# Sheet2.net
KiCad netlist of a schematic drawn in Altium Designer
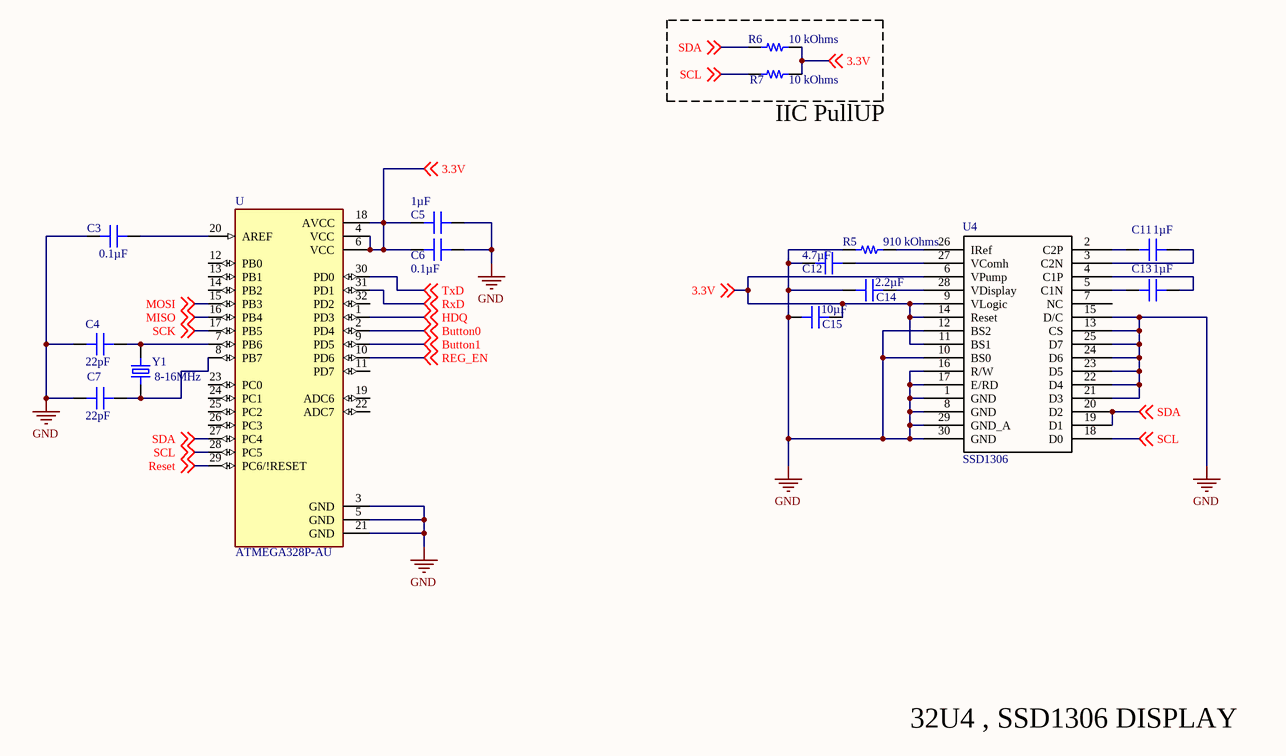
[diagram p0: Sheet2.SchDoc]

(export (version "E")
  (design (tool "Eeschema 10.0.6"))
  (components
    (comp (ref "C3")
      (value "0.1µF")
      (footprint "CAP 0402_1005")
      (description "CAP CER 10UF 10V X5R 0402")
      (fields
        (field (name "PART NUMBER") "CL05A106MP8NUB8")
        (field (name "MANUFACTURER") "Samsung Electro-Mechanics")
      )
      (libsource (lib "Celestial Altium Library - altium_library") (part "Capacitor"))
    )
    (comp (ref "C4")
      (value "22pF")
      (footprint "CAP 0402_1005")
      (description "CAP CER 10UF 10V X5R 0402")
      (fields
        (field (name "PART NUMBER") "CL05A106MP8NUB8")
        (field (name "MANUFACTURER") "Samsung Electro-Mechanics")
      )
      (libsource (lib "Celestial Altium Library - altium_library") (part "Capacitor"))
    )
    (comp (ref "C5")
      (value "1µF")
      (footprint "CAP 0402_1005")
      (description "CAP CER 10UF 10V X5R 0402")
      (fields
        (field (name "PART NUMBER") "CL05A106MP8NUB8")
        (field (name "MANUFACTURER") "Samsung Electro-Mechanics")
      )
      (libsource (lib "Celestial Altium Library - altium_library") (part "Capacitor"))
    )
    (comp (ref "C6")
      (value "0.1µF")
      (footprint "CAP 0402_1005")
      (description "CAP CER 10UF 10V X5R 0402")
      (fields
        (field (name "PART NUMBER") "CL05A106MP8NUB8")
        (field (name "MANUFACTURER") "Samsung Electro-Mechanics")
      )
      (libsource (lib "Celestial Altium Library - altium_library") (part "Capacitor"))
    )
    (comp (ref "C7")
      (value "22pF")
      (footprint "CAP 0402_1005")
      (description "CAP CER 10UF 10V X5R 0402")
      (fields
        (field (name "PART NUMBER") "CL05A106MP8NUB8")
        (field (name "MANUFACTURER") "Samsung Electro-Mechanics")
      )
      (libsource (lib "Celestial Altium Library - altium_library") (part "Capacitor"))
    )
    (comp (ref "C11")
      (value "1µF")
      (footprint "CAP 0402_1005")
      (description "CAP CER 10UF 10V X5R 0402")
      (fields
        (field (name "PART NUMBER") "CL05A106MP8NUB8")
        (field (name "MANUFACTURER") "Samsung Electro-Mechanics")
      )
      (libsource (lib "Celestial Altium Library - altium_library") (part "Capacitor"))
    )
    (comp (ref "C12")
      (value "4.7µF")
      (footprint "CAP 0402_1005")
      (description "CAP CER 10UF 10V X5R 0402")
      (fields
        (field (name "PART NUMBER") "CL05A106MP8NUB8")
        (field (name "MANUFACTURER") "Samsung Electro-Mechanics")
      )
      (libsource (lib "Celestial Altium Library - altium_library") (part "Capacitor"))
    )
    (comp (ref "C13")
      (value "1µF")
      (footprint "CAP 0402_1005")
      (description "CAP CER 10UF 10V X5R 0402")
      (fields
        (field (name "PART NUMBER") "CL05A106MP8NUB8")
        (field (name "MANUFACTURER") "Samsung Electro-Mechanics")
      )
      (libsource (lib "Celestial Altium Library - altium_library") (part "Capacitor"))
    )
    (comp (ref "C14")
      (value "2.2µF")
      (footprint "CAP 0402_1005")
      (description "CAP CER 10UF 10V X5R 0402")
      (fields
        (field (name "PART NUMBER") "CL05A106MP8NUB8")
        (field (name "MANUFACTURER") "Samsung Electro-Mechanics")
      )
      (libsource (lib "Celestial Altium Library - altium_library") (part "Capacitor"))
    )
    (comp (ref "C15")
      (value "10µF")
      (footprint "CAP 0402_1005")
      (description "CAP CER 10UF 10V X5R 0402")
      (fields
        (field (name "PART NUMBER") "CL05A106MP8NUB8")
        (field (name "MANUFACTURER") "Samsung Electro-Mechanics")
      )
      (libsource (lib "Celestial Altium Library - altium_library") (part "Capacitor"))
    )
    (comp (ref "R5")
      (value "910 kOhms")
      (footprint "RES 0402_1005")
      (description "RES 10K OHM 0.1% 1/10W 0402")
      (fields
        (field (name "PART NUMBER") "RP73PF1E10KBTD")
        (field (name "MANUFACTURER") "TE Connectivity Passive Product")
      )
      (libsource (lib "Celestial Altium Library - altium_library") (part "Resistor"))
    )
    (comp (ref "R6")
      (value "10 kOhms")
      (footprint "RES 0402_1005")
      (description "RES 10K OHM 0.1% 1/10W 0402")
      (fields
        (field (name "PART NUMBER") "RP73PF1E10KBTD")
        (field (name "MANUFACTURER") "TE Connectivity Passive Product")
      )
      (libsource (lib "Celestial Altium Library - altium_library") (part "Resistor"))
    )
    (comp (ref "R7")
      (value "10 kOhms")
      (footprint "RES 0402_1005")
      (description "RES 10K OHM 0.1% 1/10W 0402")
      (fields
        (field (name "PART NUMBER") "RP73PF1E10KBTD")
        (field (name "MANUFACTURER") "TE Connectivity Passive Product")
      )
      (libsource (lib "Celestial Altium Library - altium_library") (part "Resistor"))
    )
    (comp (ref "U")
      (value "ATMEGA328P-AU")
      (footprint "QFP80P900X900X120-32N")
      (description "AVR AVRÂ® ATmega Microcontroller IC 8-Bit 20MHz 32KB _16K x 16_ FLASH 32-TQFP _7x7_")
      (fields (field (name "MF") "Microchip Technology"))
      (libsource (lib "ATMEGA328P-AU") (part "ATMEGA328P-AU"))
    )
    (comp (ref "U4")
      (value "SSD1306")
      (footprint "PCBComponent_1")
      (libsource (lib "ugurkrcl Lib") (part "SSD1306"))
    )
    (comp (ref "Y1")
      (value "8-16MHz")
      (footprint "XTAL_ECS-80-18-4XDN")
      (description "8MHz Â±30ppm Crystal 18pF 80 Ohms HC-49/US")
      (fields (field (name "DIGI-KEY_PART_NUMBER") "X1115-ND") (field (name "MF") "ECS Inc."))
      (libsource (lib "ECS-80-18-4XDN") (part "ECS-80-18-4XDN"))
    )
  )
  (nets
    (net (code "1") (name "3.3V") (class "Default")
      (node (ref "C15") (pin "2") (pinfunction "2_2") (pintype "passive"))
      (node (ref "C5") (pin "2") (pinfunction "2_2") (pintype "passive"))
      (node (ref "C6") (pin "1") (pinfunction "1_1") (pintype "passive"))
      (node (ref "R6") (pin "1") (pinfunction "1_1") (pintype "passive"))
      (node (ref "R7") (pin "1") (pinfunction "1_1") (pintype "passive"))
      (node (ref "U") (pin "18") (pinfunction "AVCC_18") (pintype "power_in"))
      (node (ref "U") (pin "4") (pinfunction "VCC_4") (pintype "power_in"))
      (node (ref "U") (pin "6") (pinfunction "VCC_6") (pintype "power_in"))
      (node (ref "U4") (pin "11") (pinfunction "BS1_11") (pintype "passive"))
      (node (ref "U4") (pin "14") (pinfunction "Reset_14") (pintype "passive"))
      (node (ref "U4") (pin "6") (pinfunction "VPump_6") (pintype "passive"))
      (node (ref "U4") (pin "9") (pinfunction "VLogic_9") (pintype "passive"))
    )
    (net (code "2") (name "Button0") (class "Default")
      (node (ref "U") (pin "2") (pinfunction "PD4_2") (pintype "bidirectional"))
    )
    (net (code "3") (name "Button1") (class "Default")
      (node (ref "U") (pin "9") (pinfunction "PD5_9") (pintype "bidirectional"))
    )
    (net (code "4") (name "GND") (class "Default")
      (node (ref "C12") (pin "1") (pinfunction "1_1") (pintype "passive"))
      (node (ref "C14") (pin "1") (pinfunction "1_1") (pintype "passive"))
      (node (ref "C15") (pin "1") (pinfunction "1_1") (pintype "passive"))
      (node (ref "C3") (pin "2") (pinfunction "2_2") (pintype "passive"))
      (node (ref "C4") (pin "2") (pinfunction "2_2") (pintype "passive"))
      (node (ref "C5") (pin "1") (pinfunction "1_1") (pintype "passive"))
      (node (ref "C6") (pin "2") (pinfunction "2_2") (pintype "passive"))
      (node (ref "C7") (pin "2") (pinfunction "2_2") (pintype "passive"))
      (node (ref "R5") (pin "2") (pinfunction "2_2") (pintype "passive"))
      (node (ref "U") (pin "21") (pinfunction "GND_21") (pintype "power_in"))
      (node (ref "U") (pin "3") (pinfunction "GND_3") (pintype "power_in"))
      (node (ref "U") (pin "5") (pinfunction "GND_5") (pintype "power_in"))
      (node (ref "U4") (pin "1") (pinfunction "GND_1") (pintype "power_in"))
      (node (ref "U4") (pin "10") (pinfunction "BS0_10") (pintype "passive"))
      (node (ref "U4") (pin "12") (pinfunction "BS2_12") (pintype "passive"))
      (node (ref "U4") (pin "13") (pinfunction "CS_13") (pintype "passive"))
      (node (ref "U4") (pin "15") (pinfunction "D/C_15") (pintype "passive"))
      (node (ref "U4") (pin "16") (pinfunction "R/W_16") (pintype "passive"))
      (node (ref "U4") (pin "17") (pinfunction "E/RD_17") (pintype "passive"))
      (node (ref "U4") (pin "21") (pinfunction "D3_21") (pintype "passive"))
      (node (ref "U4") (pin "22") (pinfunction "D4_22") (pintype "passive"))
      (node (ref "U4") (pin "23") (pinfunction "D5_23") (pintype "passive"))
      (node (ref "U4") (pin "24") (pinfunction "D6_24") (pintype "passive"))
      (node (ref "U4") (pin "25") (pinfunction "D7_25") (pintype "passive"))
      (node (ref "U4") (pin "29") (pinfunction "GND_A_29") (pintype "power_in"))
      (node (ref "U4") (pin "30") (pinfunction "GND_30") (pintype "power_in"))
      (node (ref "U4") (pin "8") (pinfunction "GND_8") (pintype "power_in"))
    )
    (net (code "5") (name "HDQ") (class "Default")
      (node (ref "U") (pin "1") (pinfunction "PD3_1") (pintype "bidirectional"))
    )
    (net (code "6") (name "MISO") (class "Default")
      (node (ref "U") (pin "16") (pinfunction "PB4_16") (pintype "bidirectional"))
    )
    (net (code "7") (name "MOSI") (class "Default")
      (node (ref "U") (pin "15") (pinfunction "PB3_15") (pintype "bidirectional"))
    )
    (net (code "8") (name "Net-(U-AREF)") (class "Default")
      (node (ref "C3") (pin "1") (pinfunction "1_1") (pintype "passive"))
      (node (ref "U") (pin "20") (pinfunction "AREF_20") (pintype "input"))
    )
    (net (code "9") (name "Net-(U-PB6)") (class "Default")
      (node (ref "C4") (pin "1") (pinfunction "1_1") (pintype "passive"))
      (node (ref "U") (pin "7") (pinfunction "PB6_7") (pintype "bidirectional"))
      (node (ref "Y1") (pin "2") (pinfunction "2_2") (pintype "passive"))
    )
    (net (code "10") (name "Net-(U-PB7)") (class "Default")
      (node (ref "C7") (pin "1") (pinfunction "1_1") (pintype "passive"))
      (node (ref "U") (pin "8") (pinfunction "PB7_8") (pintype "bidirectional"))
      (node (ref "Y1") (pin "1") (pinfunction "1_1") (pintype "passive"))
    )
    (net (code "11") (name "Net-(U4-C1N)") (class "Default")
      (node (ref "C13") (pin "1") (pinfunction "1_1") (pintype "passive"))
      (node (ref "U4") (pin "5") (pinfunction "C1N_5") (pintype "passive"))
    )
    (net (code "12") (name "Net-(U4-C1P)") (class "Default")
      (node (ref "C13") (pin "2") (pinfunction "2_2") (pintype "passive"))
      (node (ref "U4") (pin "4") (pinfunction "C1P_4") (pintype "passive"))
    )
    (net (code "13") (name "Net-(U4-C2N)") (class "Default")
      (node (ref "C11") (pin "2") (pinfunction "2_2") (pintype "passive"))
      (node (ref "U4") (pin "3") (pinfunction "C2N_3") (pintype "passive"))
    )
    (net (code "14") (name "Net-(U4-C2P)") (class "Default")
      (node (ref "C11") (pin "1") (pinfunction "1_1") (pintype "passive"))
      (node (ref "U4") (pin "2") (pinfunction "C2P_2") (pintype "passive"))
    )
    (net (code "15") (name "Net-(U4-IRef)") (class "Default")
      (node (ref "R5") (pin "1") (pinfunction "1_1") (pintype "passive"))
      (node (ref "U4") (pin "26") (pinfunction "IRef_26") (pintype "passive"))
    )
    (net (code "16") (name "Net-(U4-VComh)") (class "Default")
      (node (ref "C12") (pin "2") (pinfunction "2_2") (pintype "passive"))
      (node (ref "U4") (pin "27") (pinfunction "VComh_27") (pintype "passive"))
    )
    (net (code "17") (name "Net-(U4-VDisplay)") (class "Default")
      (node (ref "C14") (pin "2") (pinfunction "2_2") (pintype "passive"))
      (node (ref "U4") (pin "28") (pinfunction "VDisplay_28") (pintype "passive"))
    )
    (net (code "18") (name "REG_EN") (class "Default")
      (node (ref "U") (pin "10") (pinfunction "PD6_10") (pintype "bidirectional"))
    )
    (net (code "19") (name "Reset") (class "Default")
      (node (ref "U") (pin "29") (pinfunction "PC6/!RESET_29") (pintype "bidirectional"))
    )
    (net (code "20") (name "RxD") (class "Default")
      (node (ref "U") (pin "31") (pinfunction "PD1_31") (pintype "bidirectional"))
    )
    (net (code "21") (name "SCK") (class "Default")
      (node (ref "U") (pin "17") (pinfunction "PB5_17") (pintype "bidirectional"))
    )
    (net (code "22") (name "SCL") (class "Default")
      (node (ref "R7") (pin "2") (pinfunction "2_2") (pintype "passive"))
      (node (ref "U") (pin "28") (pinfunction "PC5_28") (pintype "bidirectional"))
      (node (ref "U4") (pin "18") (pinfunction "D0_18") (pintype "passive"))
    )
    (net (code "23") (name "SDA") (class "Default")
      (node (ref "R6") (pin "2") (pinfunction "2_2") (pintype "passive"))
      (node (ref "U") (pin "27") (pinfunction "PC4_27") (pintype "bidirectional"))
      (node (ref "U4") (pin "19") (pinfunction "D1_19") (pintype "passive"))
      (node (ref "U4") (pin "20") (pinfunction "D2_20") (pintype "passive"))
    )
    (net (code "24") (name "TxD") (class "Default")
      (node (ref "U") (pin "30") (pinfunction "PD0_30") (pintype "bidirectional"))
    )
    (net (code "25") (name "unconnected-(U-ADC6-Pad19)") (class "Default")
      (node (ref "U") (pin "19") (pinfunction "ADC6_19") (pintype "bidirectional"))
    )
    (net (code "26") (name "unconnected-(U-ADC7-Pad22)") (class "Default")
      (node (ref "U") (pin "22") (pinfunction "ADC7_22") (pintype "bidirectional"))
    )
    (net (code "27") (name "unconnected-(U-PB0-Pad12)") (class "Default")
      (node (ref "U") (pin "12") (pinfunction "PB0_12") (pintype "bidirectional"))
    )
    (net (code "28") (name "unconnected-(U-PB1-Pad13)") (class "Default")
      (node (ref "U") (pin "13") (pinfunction "PB1_13") (pintype "bidirectional"))
    )
    (net (code "29") (name "unconnected-(U-PB2-Pad14)") (class "Default")
      (node (ref "U") (pin "14") (pinfunction "PB2_14") (pintype "bidirectional"))
    )
    (net (code "30") (name "unconnected-(U-PC0-Pad23)") (class "Default")
      (node (ref "U") (pin "23") (pinfunction "PC0_23") (pintype "bidirectional"))
    )
    (net (code "31") (name "unconnected-(U-PC1-Pad24)") (class "Default")
      (node (ref "U") (pin "24") (pinfunction "PC1_24") (pintype "bidirectional"))
    )
    (net (code "32") (name "unconnected-(U-PC2-Pad25)") (class "Default")
      (node (ref "U") (pin "25") (pinfunction "PC2_25") (pintype "bidirectional"))
    )
    (net (code "33") (name "unconnected-(U-PC3-Pad26)") (class "Default")
      (node (ref "U") (pin "26") (pinfunction "PC3_26") (pintype "bidirectional"))
    )
    (net (code "34") (name "unconnected-(U-PD2-Pad32)") (class "Default")
      (node (ref "U") (pin "32") (pinfunction "PD2_32") (pintype "bidirectional"))
    )
    (net (code "35") (name "unconnected-(U-PD7-Pad11)") (class "Default")
      (node (ref "U") (pin "11") (pinfunction "PD7_11") (pintype "bidirectional"))
    )
    (net (code "36") (name "unconnected-(U4-NC-Pad7)") (class "Default")
      (node (ref "U4") (pin "7") (pinfunction "NC_7") (pintype "passive"))
    )
  )
)
